# shield.net
KiCad netlist of a schematic drawn in EAGLE
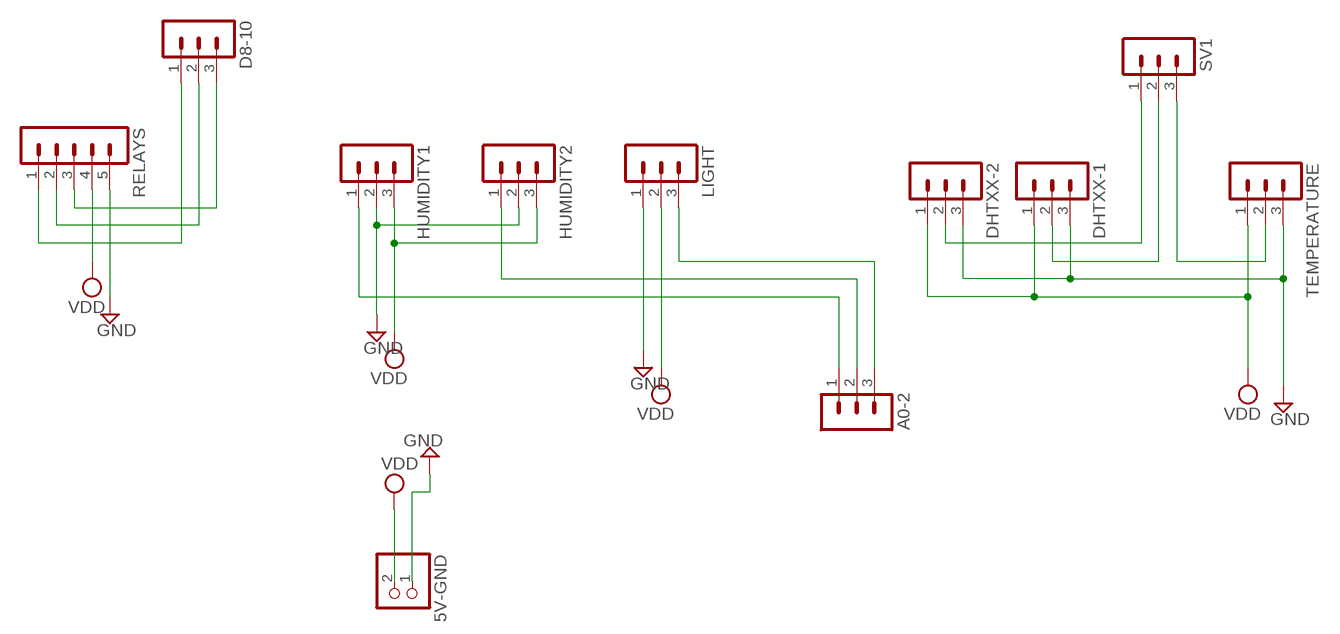
[diagram p0: schematic, sheet 1]

(export (version "E")
  (design (tool "Eeschema 10.0.6"))
  (components
    (comp (ref "5V-GND")
      (value "PINHD-1X2")
      (footprint "eagle-import:1X02")
      (libsource (lib "eagle-import") (part "PINHD-1X2"))
    )
    (comp (ref "A0-2")
      (value "MA03-1")
      (footprint "eagle-import:MA03-1")
      (libsource (lib "eagle-import") (part "MA03-1"))
    )
    (comp (ref "D8-10")
      (value "MA03-1")
      (footprint "eagle-import:MA03-1")
      (libsource (lib "eagle-import") (part "MA03-1"))
    )
    (comp (ref "DHTXX-1")
      (value "MA03-1")
      (footprint "eagle-import:MA03-1")
      (libsource (lib "eagle-import") (part "MA03-1"))
    )
    (comp (ref "DHTXX-2")
      (value "MA03-1")
      (footprint "eagle-import:MA03-1")
      (libsource (lib "eagle-import") (part "MA03-1"))
    )
    (comp (ref "HUMIDITY1")
      (value "MA03-1")
      (footprint "eagle-import:MA03-1")
      (libsource (lib "eagle-import") (part "MA03-1"))
    )
    (comp (ref "HUMIDITY2")
      (value "MA03-1")
      (footprint "eagle-import:MA03-1")
      (libsource (lib "eagle-import") (part "MA03-1"))
    )
    (comp (ref "LIGHT")
      (value "MA03-1")
      (footprint "eagle-import:MA03-1")
      (libsource (lib "eagle-import") (part "MA03-1"))
    )
    (comp (ref "RELAYS")
      (value "MA05-1")
      (footprint "eagle-import:MA05-1")
      (libsource (lib "eagle-import") (part "MA05-1"))
    )
    (comp (ref "SV1")
      (value "MA03-1")
      (footprint "eagle-import:MA03-1")
      (libsource (lib "eagle-import") (part "MA03-1"))
    )
    (comp (ref "TEMPERATURE")
      (value "MA03-1")
      (footprint "eagle-import:MA03-1")
      (libsource (lib "eagle-import") (part "MA03-1"))
    )
  )
  (nets
    (net (code "1") (name "GND") (class "Default")
      (node (ref "5V-GND") (pin "1") (pinfunction "1_1") (pintype "passive"))
      (node (ref "DHTXX-1") (pin "3") (pinfunction "3_3") (pintype "passive"))
      (node (ref "DHTXX-2") (pin "3") (pinfunction "3_3") (pintype "passive"))
      (node (ref "HUMIDITY1") (pin "2") (pinfunction "2_2") (pintype "passive"))
      (node (ref "HUMIDITY2") (pin "2") (pinfunction "2_2") (pintype "passive"))
      (node (ref "LIGHT") (pin "1") (pinfunction "1_1") (pintype "passive"))
      (node (ref "RELAYS") (pin "5") (pinfunction "5_5") (pintype "passive"))
      (node (ref "TEMPERATURE") (pin "3") (pinfunction "3_3") (pintype "passive"))
    )
    (net (code "2") (name "Net-(A0-2-Pad1)") (class "Default")
      (node (ref "A0-2") (pin "1") (pinfunction "1_1") (pintype "passive"))
      (node (ref "HUMIDITY1") (pin "1") (pinfunction "1_1") (pintype "passive"))
    )
    (net (code "3") (name "Net-(A0-2-Pad2)") (class "Default")
      (node (ref "A0-2") (pin "2") (pinfunction "2_2") (pintype "passive"))
      (node (ref "HUMIDITY2") (pin "1") (pinfunction "1_1") (pintype "passive"))
    )
    (net (code "4") (name "Net-(A0-2-Pad3)") (class "Default")
      (node (ref "A0-2") (pin "3") (pinfunction "3_3") (pintype "passive"))
      (node (ref "LIGHT") (pin "3") (pinfunction "3_3") (pintype "passive"))
    )
    (net (code "5") (name "Net-(D8-10-Pad1)") (class "Default")
      (node (ref "D8-10") (pin "1") (pinfunction "1_1") (pintype "passive"))
      (node (ref "RELAYS") (pin "1") (pinfunction "1_1") (pintype "passive"))
    )
    (net (code "6") (name "Net-(D8-10-Pad2)") (class "Default")
      (node (ref "D8-10") (pin "2") (pinfunction "2_2") (pintype "passive"))
      (node (ref "RELAYS") (pin "2") (pinfunction "2_2") (pintype "passive"))
    )
    (net (code "7") (name "Net-(D8-10-Pad3)") (class "Default")
      (node (ref "D8-10") (pin "3") (pinfunction "3_3") (pintype "passive"))
      (node (ref "RELAYS") (pin "3") (pinfunction "3_3") (pintype "passive"))
    )
    (net (code "8") (name "Net-(DHTXX-1-Pad2)") (class "Default")
      (node (ref "DHTXX-1") (pin "2") (pinfunction "2_2") (pintype "passive"))
      (node (ref "SV1") (pin "2") (pinfunction "2_2") (pintype "passive"))
    )
    (net (code "9") (name "Net-(DHTXX-2-Pad2)") (class "Default")
      (node (ref "DHTXX-2") (pin "2") (pinfunction "2_2") (pintype "passive"))
      (node (ref "SV1") (pin "1") (pinfunction "1_1") (pintype "passive"))
    )
    (net (code "10") (name "Net-(SV1-Pad3)") (class "Default")
      (node (ref "SV1") (pin "3") (pinfunction "3_3") (pintype "passive"))
      (node (ref "TEMPERATURE") (pin "2") (pinfunction "2_2") (pintype "passive"))
    )
    (net (code "11") (name "VDD") (class "Default")
      (node (ref "5V-GND") (pin "2") (pinfunction "2_2") (pintype "passive"))
      (node (ref "DHTXX-1") (pin "1") (pinfunction "1_1") (pintype "passive"))
      (node (ref "DHTXX-2") (pin "1") (pinfunction "1_1") (pintype "passive"))
      (node (ref "HUMIDITY1") (pin "3") (pinfunction "3_3") (pintype "passive"))
      (node (ref "HUMIDITY2") (pin "3") (pinfunction "3_3") (pintype "passive"))
      (node (ref "LIGHT") (pin "2") (pinfunction "2_2") (pintype "passive"))
      (node (ref "RELAYS") (pin "4") (pinfunction "4_4") (pintype "passive"))
      (node (ref "TEMPERATURE") (pin "1") (pinfunction "1_1") (pintype "passive"))
    )
  )
)
